# 4_Actuators.net
KiCad netlist of a schematic drawn in Altium Designer
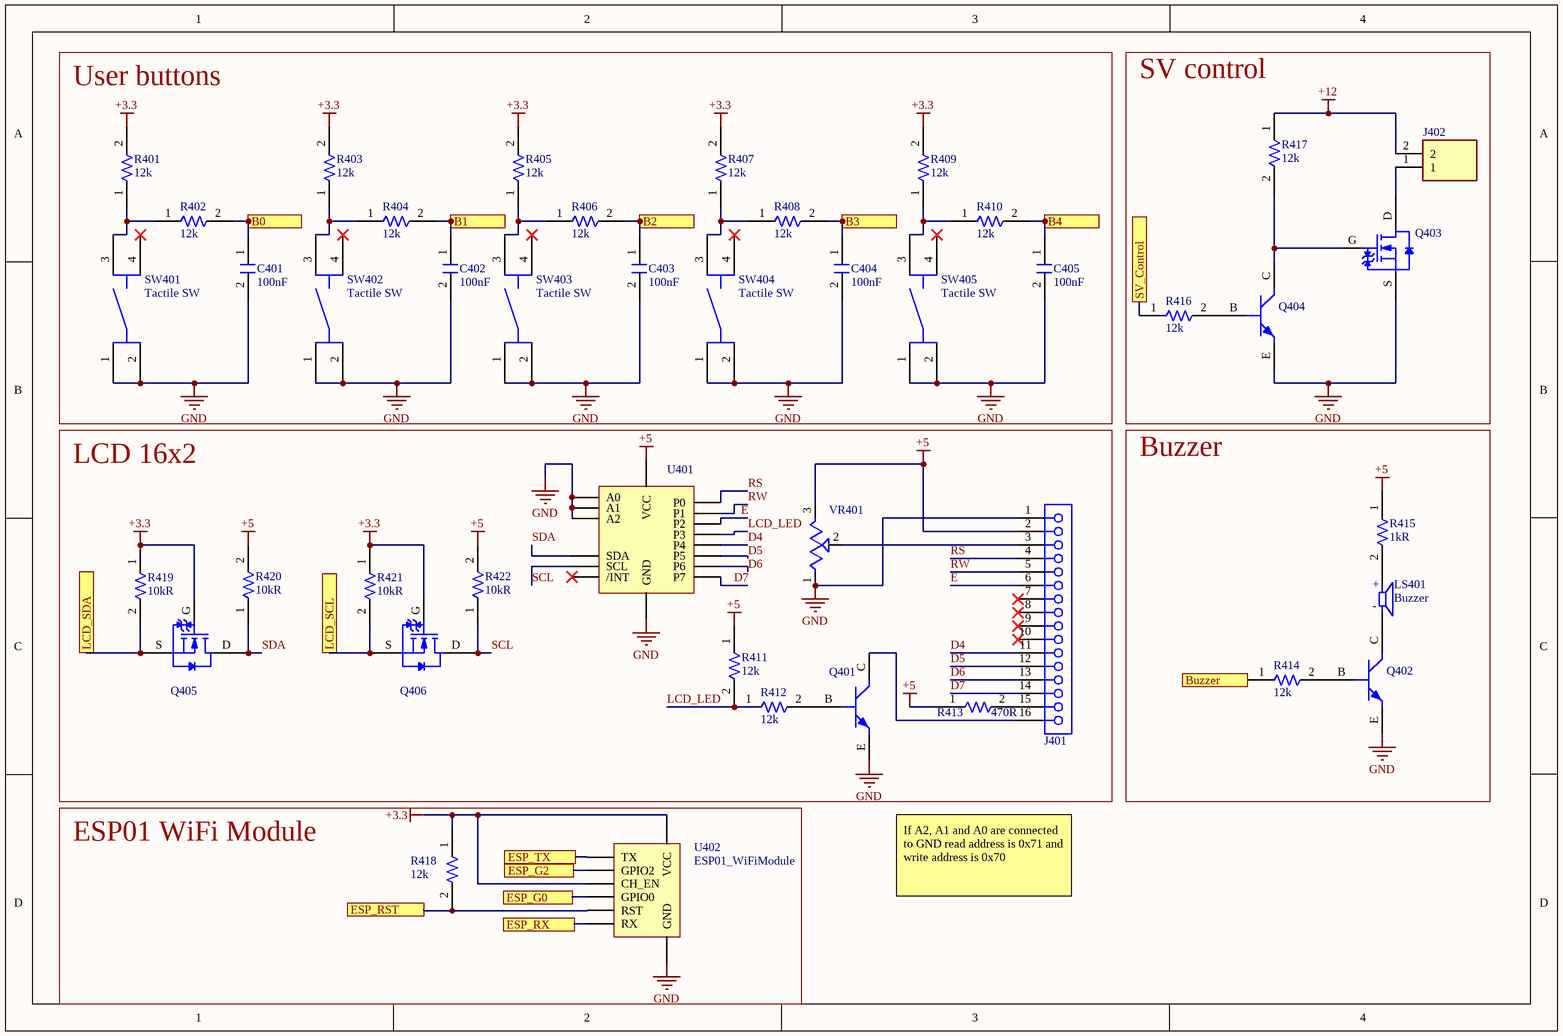
[diagram p0: [4]Actuators.SchDoc]

(export (version "E")
  (design (tool "Eeschema 10.0.6"))
  (components
    (comp (ref "C401")
      (value "885012208009")
      (footprint "C1206FNPC-RW")
      (description "Cap, 0.1ΜF, 10V, 10%, X7R, 1206")
      (fields
        (field (name "TOLERANCE") "10%")
        (field (name "CAPACITANCE") "100nF")
        (field (name ".CREATOR") "GP")
      )
      (libsource (lib "Passives") (part "C100n-10V-1206FNPC-X7R"))
    )
    (comp (ref "C402")
      (value "885012208009")
      (footprint "C1206FNPC-RW")
      (description "Cap, 0.1ΜF, 10V, 10%, X7R, 1206")
      (fields
        (field (name "TOLERANCE") "10%")
        (field (name "CAPACITANCE") "100nF")
        (field (name ".CREATOR") "GP")
      )
      (libsource (lib "Passives") (part "C100n-10V-1206FNPC-X7R"))
    )
    (comp (ref "C403")
      (value "885012208009")
      (footprint "C1206FNPC-RW")
      (description "Cap, 0.1ΜF, 10V, 10%, X7R, 1206")
      (fields
        (field (name "TOLERANCE") "10%")
        (field (name "CAPACITANCE") "100nF")
        (field (name ".CREATOR") "GP")
      )
      (libsource (lib "Passives") (part "C100n-10V-1206FNPC-X7R"))
    )
    (comp (ref "C404")
      (value "885012208009")
      (footprint "C1206FNPC-RW")
      (description "Cap, 0.1ΜF, 10V, 10%, X7R, 1206")
      (fields
        (field (name "TOLERANCE") "10%")
        (field (name "CAPACITANCE") "100nF")
        (field (name ".CREATOR") "GP")
      )
      (libsource (lib "Passives") (part "C100n-10V-1206FNPC-X7R"))
    )
    (comp (ref "C405")
      (value "885012208009")
      (footprint "C1206FNPC-RW")
      (description "Cap, 0.1ΜF, 10V, 10%, X7R, 1206")
      (fields
        (field (name "TOLERANCE") "10%")
        (field (name "CAPACITANCE") "100nF")
        (field (name ".CREATOR") "GP")
      )
      (libsource (lib "Passives") (part "C100n-10V-1206FNPC-X7R"))
    )
    (comp (ref "J401")
      (value "16 SH")
      (footprint "SocketHeader_16_254")
      (description "WR-PHD Socket Header, THT, Vertical, pitch 2.54mm, 1 Row, 16P")
      (fields
        (field (name "MANUFACTURER PART NUMBER") "61301611821")
        (field (name "MANUFACTURER") "Wurth Elektronik")
      )
      (libsource (lib "CommonFiles_Library") (part "Socket_Header_16_2.54"))
    )
    (comp (ref "J402")
      (value "J_2_CableContact")
      (footprint "TE_282834-2")
      (fields (field (name "MP") "282834-2") (field (name "MF") "{'manufacturer': u'TE Connectivity'}"))
      (libsource (lib "CommonFiles_Library") (part "J_2_CableContact"))
    )
    (comp (ref "LS401")
      (value "Buzzer")
      (footprint "CUI_CMI-1275C-050")
      (description "12 mm, 5 Vdc, 90 dB, 3.1 kHz, Through Hole, Magnetic Audio Indicator Buzzer")
      (fields (field (name "MF") "CUI Devices") (field (name "MP") "CMI-1275C-050"))
      (libsource (lib "CommonFiles_Library") (part "Buzzer_CMI-1275C-050"))
    )
    (comp (ref "Q401")
      (value "BC817-25LT1G")
      (footprint "TRT-NPN-0.5/45-SOT23")
      (description "ON Semi BC817-25LT1G NPN Bipolar Transistor; 0.5 A; 45 V; 3-Pin SOT-23")
      (fields (field (name ".CREATOR") "GP"))
      (libsource (lib "Semiconductor") (part "TRT-NPN-0.5/45-SOT23"))
    )
    (comp (ref "Q402")
      (value "BC817-25LT1G")
      (footprint "TRT-NPN-0.5/45-SOT23")
      (description "ON Semi BC817-25LT1G NPN Bipolar Transistor; 0.5 A; 45 V; 3-Pin SOT-23")
      (fields (field (name ".CREATOR") "GP"))
      (libsource (lib "Semiconductor") (part "TRT-NPN-0.5/45-SOT23"))
    )
    (comp (ref "Q403")
      (value "TRT_NCH_FDN327N")
      (footprint "SuperSOT3")
      (libsource (lib "CommonFiles_Library") (part "TRT_NCH_FDN327N"))
    )
    (comp (ref "Q404")
      (value "BC817-25LT1G")
      (footprint "TRT-NPN-0.5/45-SOT23")
      (description "ON Semi BC817-25LT1G NPN Bipolar Transistor; 0.5 A; 45 V; 3-Pin SOT-23")
      (fields (field (name ".CREATOR") "GP"))
      (libsource (lib "Semiconductor") (part "TRT-NPN-0.5/45-SOT23"))
    )
    (comp (ref "Q405")
      (value "TRT_NCH_FDN327N")
      (footprint "SuperSOT3")
      (libsource (lib "CommonFiles_Library") (part "TRT_NCH_FDN327N"))
    )
    (comp (ref "Q406")
      (value "TRT_NCH_FDN327N")
      (footprint "SuperSOT3")
      (libsource (lib "CommonFiles_Library") (part "TRT_NCH_FDN327N"))
    )
    (comp (ref "R401")
      (value "12k")
      (footprint "R1206")
      (libsource (lib "CommonFiles_Library") (part "R12k-1206"))
    )
    (comp (ref "R402")
      (value "12k")
      (footprint "R1206")
      (libsource (lib "CommonFiles_Library") (part "R12k-1206"))
    )
    (comp (ref "R403")
      (value "12k")
      (footprint "R1206")
      (libsource (lib "CommonFiles_Library") (part "R12k-1206"))
    )
    (comp (ref "R404")
      (value "12k")
      (footprint "R1206")
      (libsource (lib "CommonFiles_Library") (part "R12k-1206"))
    )
    (comp (ref "R405")
      (value "12k")
      (footprint "R1206")
      (libsource (lib "CommonFiles_Library") (part "R12k-1206"))
    )
    (comp (ref "R406")
      (value "12k")
      (footprint "R1206")
      (libsource (lib "CommonFiles_Library") (part "R12k-1206"))
    )
    (comp (ref "R407")
      (value "12k")
      (footprint "R1206")
      (libsource (lib "CommonFiles_Library") (part "R12k-1206"))
    )
    (comp (ref "R408")
      (value "12k")
      (footprint "R1206")
      (libsource (lib "CommonFiles_Library") (part "R12k-1206"))
    )
    (comp (ref "R409")
      (value "12k")
      (footprint "R1206")
      (libsource (lib "CommonFiles_Library") (part "R12k-1206"))
    )
    (comp (ref "R410")
      (value "12k")
      (footprint "R1206")
      (libsource (lib "CommonFiles_Library") (part "R12k-1206"))
    )
    (comp (ref "R411")
      (value "12k")
      (footprint "R1206")
      (libsource (lib "CommonFiles_Library") (part "R12k-1206"))
    )
    (comp (ref "R412")
      (value "12k")
      (footprint "R1206")
      (libsource (lib "CommonFiles_Library") (part "R12k-1206"))
    )
    (comp (ref "R413")
      (value "CR0805-FX-4700GLF")
      (footprint "R0805FTK")
      (description "Res Thick Film 0805 470 Ohm 1% 1/8W ±100ppm/°C Molded SMD SMD Paper Tape on Plastic Reel")
      (fields
        (field (name "TOLERANCE") "1%")
        (field (name "RESISTANCE") "470R")
        (field (name ".CREATOR") "DR")
      )
      (libsource (lib "Passives") (part "R470-0805FTK"))
    )
    (comp (ref "R414")
      (value "12k")
      (footprint "R1206")
      (libsource (lib "CommonFiles_Library") (part "R12k-1206"))
    )
    (comp (ref "R415")
      (value "CR0805-JW-102ELF")
      (footprint "R0805FTK")
      (description "Res Thick Film 0805 1K Ohm 5% 1/8W ±200ppm/°C Molded SMD SMD Paper Tape on Plastic Reel")
      (fields
        (field (name "TOLERANCE") "5%")
        (field (name "RESISTANCE") "1kR")
        (field (name ".CREATOR") "GP")
      )
      (libsource (lib "Passives") (part "R1k-0805FTK"))
    )
    (comp (ref "R416")
      (value "12k")
      (footprint "R1206")
      (libsource (lib "CommonFiles_Library") (part "R12k-1206"))
    )
    (comp (ref "R417")
      (value "12k")
      (footprint "R1206")
      (libsource (lib "CommonFiles_Library") (part "R12k-1206"))
    )
    (comp (ref "R418")
      (value "12k")
      (footprint "R1206")
      (libsource (lib "CommonFiles_Library") (part "R12k-1206"))
    )
    (comp (ref "R419")
      (value "CR0805-JW-103ELF")
      (footprint "R0805FTK")
      (fields
        (field (name "TOLERANCE") "5%")
        (field (name "RESISTANCE") "10kR")
        (field (name ".CREATOR") "DR")
      )
      (libsource (lib "Passives") (part "R10k-0805FTK"))
    )
    (comp (ref "R420")
      (value "CR0805-JW-103ELF")
      (footprint "R0805FTK")
      (fields
        (field (name "TOLERANCE") "5%")
        (field (name "RESISTANCE") "10kR")
        (field (name ".CREATOR") "DR")
      )
      (libsource (lib "Passives") (part "R10k-0805FTK"))
    )
    (comp (ref "R421")
      (value "CR0805-JW-103ELF")
      (footprint "R0805FTK")
      (fields
        (field (name "TOLERANCE") "5%")
        (field (name "RESISTANCE") "10kR")
        (field (name ".CREATOR") "DR")
      )
      (libsource (lib "Passives") (part "R10k-0805FTK"))
    )
    (comp (ref "R422")
      (value "CR0805-JW-103ELF")
      (footprint "R0805FTK")
      (fields
        (field (name "TOLERANCE") "5%")
        (field (name "RESISTANCE") "10kR")
        (field (name ".CREATOR") "DR")
      )
      (libsource (lib "Passives") (part "R10k-0805FTK"))
    )
    (comp (ref "SW401")
      (value "Tactile SW")
      (footprint "SW_2-1437565-7")
      (libsource (lib "CommonFiles_Library") (part "SW_6x6"))
    )
    (comp (ref "SW402")
      (value "Tactile SW")
      (footprint "SW_2-1437565-7")
      (libsource (lib "CommonFiles_Library") (part "SW_6x6"))
    )
    (comp (ref "SW403")
      (value "Tactile SW")
      (footprint "SW_2-1437565-7")
      (libsource (lib "CommonFiles_Library") (part "SW_6x6"))
    )
    (comp (ref "SW404")
      (value "Tactile SW")
      (footprint "SW_2-1437565-7")
      (libsource (lib "CommonFiles_Library") (part "SW_6x6"))
    )
    (comp (ref "SW405")
      (value "Tactile SW")
      (footprint "SW_2-1437565-7")
      (libsource (lib "CommonFiles_Library") (part "SW_6x6"))
    )
    (comp (ref "U401")
      (value "PCF8574ADW_I2C_8bit_I/O_Expander")
      (footprint "PCF8574A_SOIC16")
      (libsource (lib "CommonFiles_Library") (part "PCF8574ADW_I2C_8bit_I/O_Expander"))
    )
    (comp (ref "U402")
      (value "ESP01_WiFiModule")
      (footprint "Dual socket header 8 pins")
      (libsource (lib "CommonFiles_Library") (part "ESP01_WiFiModule"))
    )
    (comp (ref "VR401")
      (value "Trimmer_10k_THT")
      (footprint "TRIM_3362P-1-103LF")
      (description "Trimmer, Cermet, Rest 10 Kilohms, PCB, 1 Turns, Pwr-Rtg 0.5 W, Tol 10% ¦ Bourns 3362P-1-103LF")
      (fields (field (name "MF") "Bourns") (field (name "MP") "3362P-1-103LF"))
      (libsource (lib "CommonFiles_Library") (part "Trimmer_10k_THT"))
    )
  )
  (nets
    (net (code "1") (name "+3.3") (class "Default")
      (node (ref "Q405") (pin "G") (pinfunction "G_G") (pintype "passive"))
      (node (ref "Q406") (pin "G") (pinfunction "G_G") (pintype "passive"))
      (node (ref "R401") (pin "2") (pinfunction "2_2") (pintype "passive"))
      (node (ref "R403") (pin "2") (pinfunction "2_2") (pintype "passive"))
      (node (ref "R405") (pin "2") (pinfunction "2_2") (pintype "passive"))
      (node (ref "R407") (pin "2") (pinfunction "2_2") (pintype "passive"))
      (node (ref "R409") (pin "2") (pinfunction "2_2") (pintype "passive"))
      (node (ref "R418") (pin "1") (pinfunction "2_1") (pintype "passive"))
      (node (ref "R419") (pin "1") (pinfunction "1_1") (pintype "passive"))
      (node (ref "R421") (pin "1") (pinfunction "1_1") (pintype "passive"))
      (node (ref "U402") (pin "4") (pinfunction "CH_EN_4") (pintype "passive"))
      (node (ref "U402") (pin "8") (pinfunction "VCC_8") (pintype "passive"))
    )
    (net (code "2") (name "+5") (class "Default")
      (node (ref "J401") (pin "2") (pinfunction "2_2") (pintype "passive"))
      (node (ref "R411") (pin "1") (pinfunction "2_1") (pintype "passive"))
      (node (ref "R413") (pin "1") (pinfunction "1_1") (pintype "passive"))
      (node (ref "R415") (pin "1") (pinfunction "1_1") (pintype "passive"))
      (node (ref "R420") (pin "2") (pinfunction "2_2") (pintype "passive"))
      (node (ref "R422") (pin "2") (pinfunction "2_2") (pintype "passive"))
      (node (ref "U401") (pin "16") (pinfunction "VCC_16") (pintype "passive"))
      (node (ref "VR401") (pin "3") (pinfunction "CW_3") (pintype "passive"))
    )
    (net (code "3") (name "+12") (class "Default")
      (node (ref "J402") (pin "2") (pinfunction "2_2") (pintype "passive"))
      (node (ref "R417") (pin "1") (pinfunction "2_1") (pintype "passive"))
    )
    (net (code "4") (name "/B0") (class "Default")
      (node (ref "C401") (pin "1") (pinfunction "1_1") (pintype "passive"))
      (node (ref "R402") (pin "2") (pinfunction "2_2") (pintype "passive"))
    )
    (net (code "5") (name "/B1") (class "Default")
      (node (ref "C402") (pin "1") (pinfunction "1_1") (pintype "passive"))
      (node (ref "R404") (pin "2") (pinfunction "2_2") (pintype "passive"))
    )
    (net (code "6") (name "/B2") (class "Default")
      (node (ref "C403") (pin "1") (pinfunction "1_1") (pintype "passive"))
      (node (ref "R406") (pin "2") (pinfunction "2_2") (pintype "passive"))
    )
    (net (code "7") (name "/B3") (class "Default")
      (node (ref "C404") (pin "1") (pinfunction "1_1") (pintype "passive"))
      (node (ref "R408") (pin "2") (pinfunction "2_2") (pintype "passive"))
    )
    (net (code "8") (name "/B4") (class "Default")
      (node (ref "C405") (pin "1") (pinfunction "1_1") (pintype "passive"))
      (node (ref "R410") (pin "2") (pinfunction "2_2") (pintype "passive"))
    )
    (net (code "9") (name "/Buzzer") (class "Default")
      (node (ref "R414") (pin "1") (pinfunction "2_1") (pintype "passive"))
    )
    (net (code "10") (name "/D4") (class "Default")
      (node (ref "J401") (pin "11") (pinfunction "11_11") (pintype "passive"))
      (node (ref "U401") (pin "9") (pinfunction "P4_9") (pintype "passive"))
    )
    (net (code "11") (name "/D5") (class "Default")
      (node (ref "J401") (pin "12") (pinfunction "12_12") (pintype "passive"))
      (node (ref "U401") (pin "10") (pinfunction "P5_10") (pintype "passive"))
    )
    (net (code "12") (name "/D6") (class "Default")
      (node (ref "J401") (pin "13") (pinfunction "13_13") (pintype "passive"))
      (node (ref "U401") (pin "11") (pinfunction "P6_11") (pintype "passive"))
    )
    (net (code "13") (name "/D7") (class "Default")
      (node (ref "J401") (pin "14") (pinfunction "14_14") (pintype "passive"))
      (node (ref "U401") (pin "12") (pinfunction "P7_12") (pintype "passive"))
    )
    (net (code "14") (name "/E") (class "Default")
      (node (ref "J401") (pin "6") (pinfunction "6_6") (pintype "passive"))
      (node (ref "U401") (pin "6") (pinfunction "P2_6") (pintype "passive"))
    )
    (net (code "15") (name "/ESP_G0") (class "Default")
      (node (ref "U402") (pin "5") (pinfunction "GPIO0_5") (pintype "passive"))
    )
    (net (code "16") (name "/ESP_G2") (class "Default")
      (node (ref "U402") (pin "3") (pinfunction "GPIO2_3") (pintype "passive"))
    )
    (net (code "17") (name "/ESP_RST") (class "Default")
      (node (ref "R418") (pin "2") (pinfunction "2_2") (pintype "passive"))
      (node (ref "U402") (pin "6") (pinfunction "RST_6") (pintype "passive"))
    )
    (net (code "18") (name "/ESP_RX") (class "Default")
      (node (ref "U402") (pin "7") (pinfunction "RX_7") (pintype "passive"))
    )
    (net (code "19") (name "/ESP_TX") (class "Default")
      (node (ref "U402") (pin "2") (pinfunction "TX_2") (pintype "passive"))
    )
    (net (code "20") (name "/LCD_LED") (class "Default")
      (node (ref "R411") (pin "2") (pinfunction "2_2") (pintype "passive"))
      (node (ref "R412") (pin "1") (pinfunction "2_1") (pintype "passive"))
      (node (ref "U401") (pin "7") (pinfunction "P3_7") (pintype "passive"))
    )
    (net (code "21") (name "/LCD_SCL") (class "Default")
      (node (ref "Q406") (pin "S") (pinfunction "S_S") (pintype "passive"))
      (node (ref "R421") (pin "2") (pinfunction "2_2") (pintype "passive"))
    )
    (net (code "22") (name "/LCD_SDA") (class "Default")
      (node (ref "Q405") (pin "S") (pinfunction "S_S") (pintype "passive"))
      (node (ref "R419") (pin "2") (pinfunction "2_2") (pintype "passive"))
    )
    (net (code "23") (name "/RS") (class "Default")
      (node (ref "J401") (pin "4") (pinfunction "4_4") (pintype "passive"))
      (node (ref "U401") (pin "4") (pinfunction "P0_4") (pintype "passive"))
    )
    (net (code "24") (name "/RW") (class "Default")
      (node (ref "J401") (pin "5") (pinfunction "5_5") (pintype "passive"))
      (node (ref "U401") (pin "5") (pinfunction "P1_5") (pintype "passive"))
    )
    (net (code "25") (name "/SCL") (class "Default")
      (node (ref "Q406") (pin "D") (pinfunction "D_D") (pintype "passive"))
      (node (ref "R422") (pin "1") (pinfunction "1_1") (pintype "passive"))
      (node (ref "U401") (pin "14") (pinfunction "SCL_14") (pintype "passive"))
    )
    (net (code "26") (name "/SDA") (class "Default")
      (node (ref "Q405") (pin "D") (pinfunction "D_D") (pintype "passive"))
      (node (ref "R420") (pin "1") (pinfunction "1_1") (pintype "passive"))
      (node (ref "U401") (pin "15") (pinfunction "SDA_15") (pintype "passive"))
    )
    (net (code "27") (name "/SV_Control") (class "Default")
      (node (ref "R416") (pin "1") (pinfunction "2_1") (pintype "passive"))
    )
    (net (code "28") (name "GND") (class "Default")
      (node (ref "C401") (pin "2") (pinfunction "2_2") (pintype "passive"))
      (node (ref "C402") (pin "2") (pinfunction "2_2") (pintype "passive"))
      (node (ref "C403") (pin "2") (pinfunction "2_2") (pintype "passive"))
      (node (ref "C404") (pin "2") (pinfunction "2_2") (pintype "passive"))
      (node (ref "C405") (pin "2") (pinfunction "2_2") (pintype "passive"))
      (node (ref "J401") (pin "1") (pinfunction "1_1") (pintype "passive"))
      (node (ref "Q401") (pin "E") (pinfunction "E_E") (pintype "passive"))
      (node (ref "Q402") (pin "E") (pinfunction "E_E") (pintype "passive"))
      (node (ref "Q403") (pin "S") (pinfunction "S_S") (pintype "passive"))
      (node (ref "Q404") (pin "E") (pinfunction "E_E") (pintype "passive"))
      (node (ref "SW401") (pin "1") (pinfunction "1_1") (pintype "passive"))
      (node (ref "SW401") (pin "2") (pinfunction "2_2") (pintype "passive"))
      (node (ref "SW402") (pin "1") (pinfunction "1_1") (pintype "passive"))
      (node (ref "SW402") (pin "2") (pinfunction "2_2") (pintype "passive"))
      (node (ref "SW403") (pin "1") (pinfunction "1_1") (pintype "passive"))
      (node (ref "SW403") (pin "2") (pinfunction "2_2") (pintype "passive"))
      (node (ref "SW404") (pin "1") (pinfunction "1_1") (pintype "passive"))
      (node (ref "SW404") (pin "2") (pinfunction "2_2") (pintype "passive"))
      (node (ref "SW405") (pin "1") (pinfunction "1_1") (pintype "passive"))
      (node (ref "SW405") (pin "2") (pinfunction "2_2") (pintype "passive"))
      (node (ref "U401") (pin "1") (pinfunction "A0_1") (pintype "passive"))
      (node (ref "U401") (pin "2") (pinfunction "A1_2") (pintype "passive"))
      (node (ref "U401") (pin "3") (pinfunction "A2_3") (pintype "passive"))
      (node (ref "U401") (pin "8") (pinfunction "GND_8") (pintype "passive"))
      (node (ref "U402") (pin "1") (pinfunction "GND_1") (pintype "passive"))
      (node (ref "VR401") (pin "1") (pinfunction "CCW_1") (pintype "passive"))
    )
    (net (code "29") (name "Net-(J401-Pad15)") (class "Default")
      (node (ref "J401") (pin "15") (pinfunction "15_15") (pintype "passive"))
      (node (ref "R413") (pin "2") (pinfunction "2_2") (pintype "passive"))
    )
    (net (code "30") (name "Net-(J401-Pad16)") (class "Default")
      (node (ref "J401") (pin "16") (pinfunction "16_16") (pintype "passive"))
      (node (ref "Q401") (pin "C") (pinfunction "C_C") (pintype "passive"))
    )
    (net (code "31") (name "Net-(J402-Pad1)") (class "Default")
      (node (ref "J402") (pin "1") (pinfunction "1_1") (pintype "passive"))
      (node (ref "Q403") (pin "D") (pinfunction "D_D") (pintype "passive"))
    )
    (net (code "32") (name "Net-(LS401-PadN)") (class "Default")
      (node (ref "LS401") (pin "N") (pinfunction "N_N") (pintype "passive"))
      (node (ref "Q402") (pin "C") (pinfunction "C_C") (pintype "passive"))
    )
    (net (code "33") (name "Net-(LS401-PadP)") (class "Default")
      (node (ref "LS401") (pin "P") (pinfunction "P_P") (pintype "passive"))
      (node (ref "R415") (pin "2") (pinfunction "2_2") (pintype "passive"))
    )
    (net (code "34") (name "Net-(Q401-PadB)") (class "Default")
      (node (ref "Q401") (pin "B") (pinfunction "B_B") (pintype "passive"))
      (node (ref "R412") (pin "2") (pinfunction "2_2") (pintype "passive"))
    )
    (net (code "35") (name "Net-(Q402-PadB)") (class "Default")
      (node (ref "Q402") (pin "B") (pinfunction "B_B") (pintype "passive"))
      (node (ref "R414") (pin "2") (pinfunction "2_2") (pintype "passive"))
    )
    (net (code "36") (name "Net-(Q403-PadG)") (class "Default")
      (node (ref "Q403") (pin "G") (pinfunction "G_G") (pintype "passive"))
      (node (ref "Q404") (pin "C") (pinfunction "C_C") (pintype "passive"))
      (node (ref "R417") (pin "2") (pinfunction "2_2") (pintype "passive"))
    )
    (net (code "37") (name "Net-(Q404-PadB)") (class "Default")
      (node (ref "Q404") (pin "B") (pinfunction "B_B") (pintype "passive"))
      (node (ref "R416") (pin "2") (pinfunction "2_2") (pintype "passive"))
    )
    (net (code "38") (name "Net-(R401-2-Pad1)") (class "Default")
      (node (ref "R401") (pin "1") (pinfunction "2_1") (pintype "passive"))
      (node (ref "R402") (pin "1") (pinfunction "2_1") (pintype "passive"))
      (node (ref "SW401") (pin "3") (pinfunction "3_3") (pintype "passive"))
    )
    (net (code "39") (name "Net-(R403-2-Pad1)") (class "Default")
      (node (ref "R403") (pin "1") (pinfunction "2_1") (pintype "passive"))
      (node (ref "R404") (pin "1") (pinfunction "2_1") (pintype "passive"))
      (node (ref "SW402") (pin "3") (pinfunction "3_3") (pintype "passive"))
    )
    (net (code "40") (name "Net-(R405-2-Pad1)") (class "Default")
      (node (ref "R405") (pin "1") (pinfunction "2_1") (pintype "passive"))
      (node (ref "R406") (pin "1") (pinfunction "2_1") (pintype "passive"))
      (node (ref "SW403") (pin "3") (pinfunction "3_3") (pintype "passive"))
    )
    (net (code "41") (name "Net-(R407-2-Pad1)") (class "Default")
      (node (ref "R407") (pin "1") (pinfunction "2_1") (pintype "passive"))
      (node (ref "R408") (pin "1") (pinfunction "2_1") (pintype "passive"))
      (node (ref "SW404") (pin "3") (pinfunction "3_3") (pintype "passive"))
    )
    (net (code "42") (name "Net-(R409-2-Pad1)") (class "Default")
      (node (ref "R409") (pin "1") (pinfunction "2_1") (pintype "passive"))
      (node (ref "R410") (pin "1") (pinfunction "2_1") (pintype "passive"))
      (node (ref "SW405") (pin "3") (pinfunction "3_3") (pintype "passive"))
    )
    (net (code "43") (name "Net-(VR401-WIPER)") (class "Default")
      (node (ref "J401") (pin "3") (pinfunction "3_3") (pintype "passive"))
      (node (ref "VR401") (pin "2") (pinfunction "WIPER_2") (pintype "passive"))
    )
    (net (code "44") (name "unconnected-(J401-Pad7)") (class "Default")
      (node (ref "J401") (pin "7") (pinfunction "7_7") (pintype "passive+no_connect"))
    )
    (net (code "45") (name "unconnected-(J401-Pad8)") (class "Default")
      (node (ref "J401") (pin "8") (pinfunction "8_8") (pintype "passive+no_connect"))
    )
    (net (code "46") (name "unconnected-(J401-Pad9)") (class "Default")
      (node (ref "J401") (pin "9") (pinfunction "9_9") (pintype "passive+no_connect"))
    )
    (net (code "47") (name "unconnected-(J401-Pad10)") (class "Default")
      (node (ref "J401") (pin "10") (pinfunction "10_10") (pintype "passive+no_connect"))
    )
    (net (code "48") (name "unconnected-(SW401-Pad4)") (class "Default")
      (node (ref "SW401") (pin "4") (pinfunction "4_4") (pintype "passive+no_connect"))
    )
    (net (code "49") (name "unconnected-(SW402-Pad4)") (class "Default")
      (node (ref "SW402") (pin "4") (pinfunction "4_4") (pintype "passive+no_connect"))
    )
    (net (code "50") (name "unconnected-(SW403-Pad4)") (class "Default")
      (node (ref "SW403") (pin "4") (pinfunction "4_4") (pintype "passive+no_connect"))
    )
    (net (code "51") (name "unconnected-(SW404-Pad4)") (class "Default")
      (node (ref "SW404") (pin "4") (pinfunction "4_4") (pintype "passive+no_connect"))
    )
    (net (code "52") (name "unconnected-(SW405-Pad4)") (class "Default")
      (node (ref "SW405") (pin "4") (pinfunction "4_4") (pintype "passive+no_connect"))
    )
    (net (code "53") (name "unconnected-(U401-{slash}INT-Pad13)") (class "Default")
      (node (ref "U401") (pin "13") (pinfunction "/INT_13") (pintype "passive+no_connect"))
    )
  )
)
